# ha_light_swich.net
KiCad netlist of a schematic drawn in Altium Designer
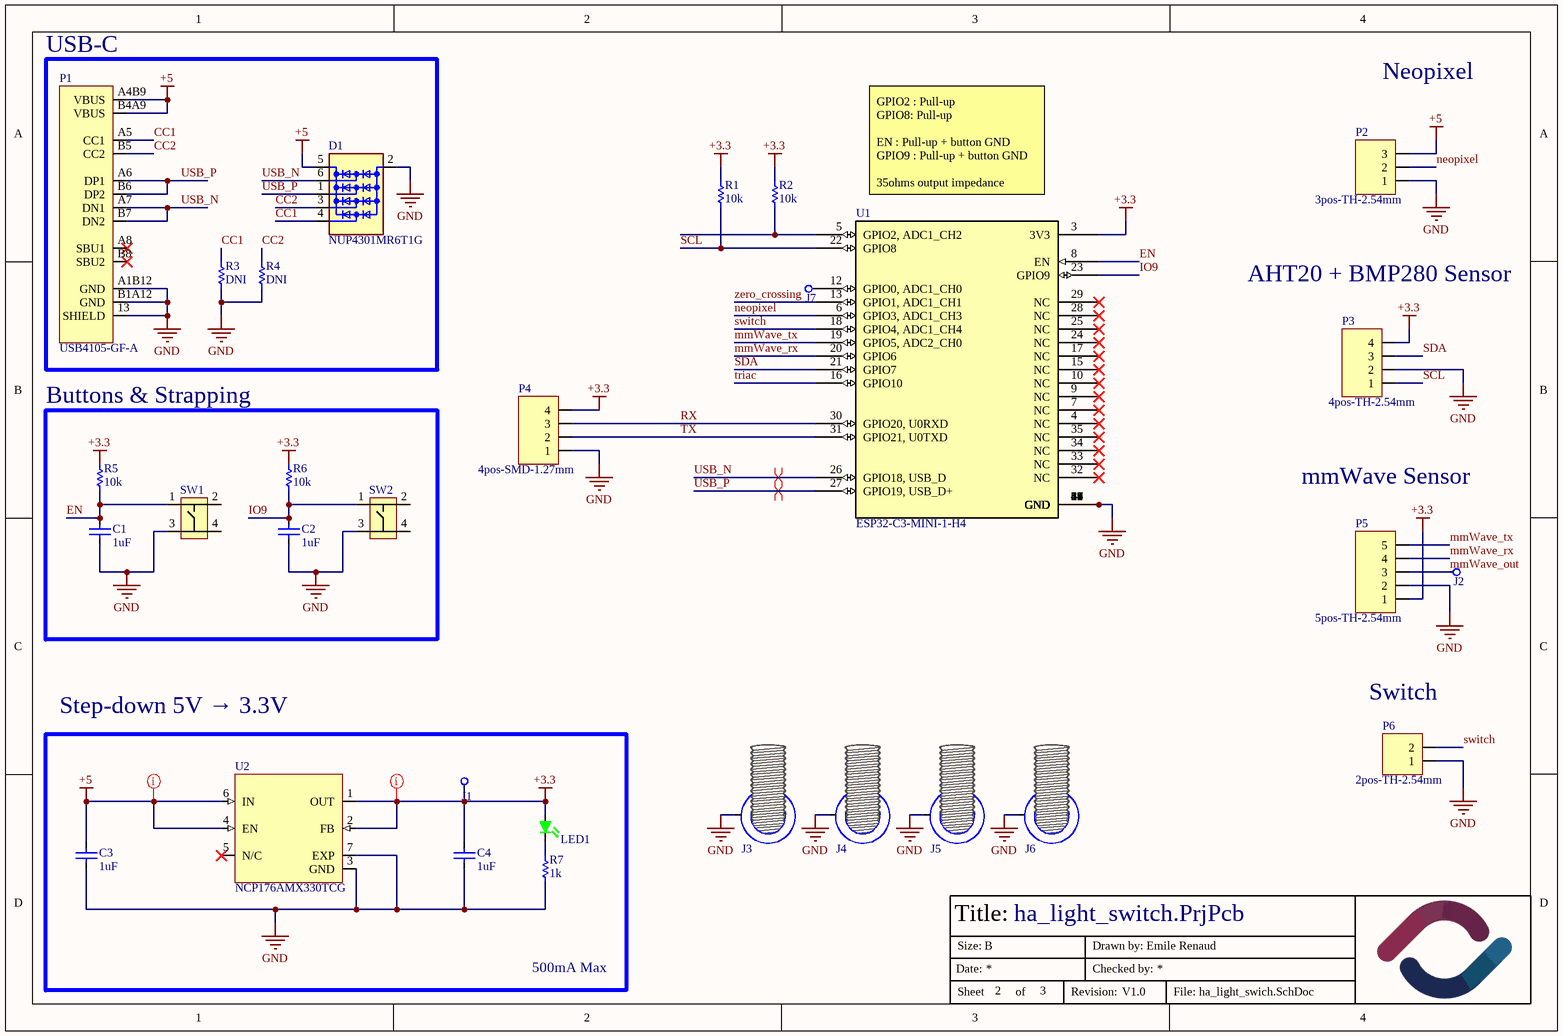
[diagram p0: ha_light_swich.SchDoc]

(export (version "E")
  (design (tool "Eeschema 10.0.6"))
  (components
    (comp (ref "C1")
      (value "1uF")
      (footprint "CAPACITOR-0603")
      (description "Capacitor-0603-1uF-25V-X5R")
      (libsource (lib "Capacitors") (part "Capacitor-0603-1uF-25V-X5R"))
    )
    (comp (ref "C2")
      (value "1uF")
      (footprint "CAPACITOR-0603")
      (description "Capacitor-0603-1uF-25V-X5R")
      (libsource (lib "Capacitors") (part "Capacitor-0603-1uF-25V-X5R"))
    )
    (comp (ref "C3")
      (value "1uF")
      (footprint "CAPACITOR-0603")
      (description "Capacitor-0603-1uF-25V-X5R")
      (libsource (lib "Capacitors") (part "Capacitor-0603-1uF-25V-X5R"))
    )
    (comp (ref "C4")
      (value "1uF")
      (footprint "CAPACITOR-0603")
      (description "Capacitor-0603-1uF-25V-X5R")
      (libsource (lib "Capacitors") (part "Capacitor-0603-1uF-25V-X5R"))
    )
    (comp (ref "D1")
      (value "NUP4301MR6T1G")
      (footprint "SOT-23-6")
      (description "4CH Clamp Ipp Tvs Diode Surface Mount SOT23-6 (SC74)")
      (libsource (lib "diodes") (part "NUP4301MR6T1G"))
    )
    (comp (ref "J1")
      (value "hole")
      (footprint "PAD-1.2MM-silk")
      (libsource (lib "JumpersAndHoles") (part "PAD 1.2mm"))
    )
    (comp (ref "J2")
      (value "hole")
      (footprint "PCB_Footprints:PAD-1.2MM")
      (libsource (lib "JumpersAndHoles") (part "PAD 1.2mm"))
    )
    (comp (ref "J3")
      (value "hole")
      (footprint "HOLE-3.40MM-M3-8MMEYELET")
      (description "Hole for M3 Bolt with 8mm pad")
      (libsource (lib "JumpersAndHoles") (part "Hole 3.40mm M3-Eyelet"))
    )
    (comp (ref "J4")
      (value "hole")
      (footprint "HOLE-3.40MM-M3-8MMEYELET")
      (description "Hole for M3 Bolt with 8mm pad")
      (libsource (lib "JumpersAndHoles") (part "Hole 3.40mm M3-Eyelet"))
    )
    (comp (ref "J5")
      (value "hole")
      (footprint "HOLE-3.40MM-M3-8MMEYELET")
      (description "Hole for M3 Bolt with 8mm pad")
      (libsource (lib "JumpersAndHoles") (part "Hole 3.40mm M3-Eyelet"))
    )
    (comp (ref "J6")
      (value "hole")
      (footprint "HOLE-3.40MM-M3-8MMEYELET")
      (description "Hole for M3 Bolt with 8mm pad")
      (libsource (lib "JumpersAndHoles") (part "Hole 3.40mm M3-Eyelet"))
    )
    (comp (ref "J7")
      (value "hole")
      (footprint "PCB_Footprints:PAD-1.2MM")
      (libsource (lib "JumpersAndHoles") (part "PAD 1.2mm"))
    )
    (comp (ref "LED1")
      (value "3147-B1911NG--20D000214U1930CT-ND")
      (footprint "LED-0603-2PIN-SILKSCREEN")
      (description "LED GREEN DIFFUSED 0603 SMD")
      (libsource (lib "LEDs") (part "LED_GREEN"))
    )
    (comp (ref "P1")
      (value "USB4105-GF-A")
      (footprint "USB-C")
      (description "CONN RCP USB2.0 TYP C 24P SMD RA\r\n5A")
      (libsource (lib "PC-connector") (part "USB4105-GF-A"))
    )
    (comp (ref "P2")
      (value "3pos-TH-2.54mm")
      (footprint "HDR1X3")
      (description "3pos TH 2.54mm Header")
      (libsource (lib "Header") (part "3pos-TH-2.54mm"))
    )
    (comp (ref "P3")
      (value "4pos-TH-2.54mm")
      (footprint "HDR1X4")
      (description "4pos TH 2.54mm Header")
      (libsource (lib "Header") (part "4pos-TH-2.54mm"))
    )
    (comp (ref "P4")
      (value "4pos-SMD-1.27mm")
      (footprint "HDR1X4-SMD-50mils")
      (description "4pos SMD 1.27mm")
      (libsource (lib "Header") (part "4pos-SMD-1.27mm"))
    )
    (comp (ref "P5")
      (value "5pos-TH-2.54mm")
      (footprint "HDR1X5")
      (description "5pos TH 2.54mm Header")
      (libsource (lib "Header") (part "5pos-TH-2.54mm"))
    )
    (comp (ref "P6")
      (value "2pos-TH-2.54mm")
      (footprint "HDR1X2")
      (description "2pos TH 2.54mm Header")
      (libsource (lib "Header") (part "2pos-TH-2.54mm"))
    )
    (comp (ref "R1")
      (value "10k")
      (footprint "Resistor-0603")
      (description "Resistor0603-10k")
      (fields (field (name "Comment") "SMT resistor"))
      (libsource (lib "Resistors") (part "Resistor0603-10k"))
    )
    (comp (ref "R2")
      (value "10k")
      (footprint "Resistor-0603")
      (description "Resistor0603-10k")
      (fields (field (name "Comment") "SMT resistor"))
      (libsource (lib "Resistors") (part "Resistor0603-10k"))
    )
    (comp (ref "R3")
      (value "DNI")
      (footprint "RESISTOR-0603")
      (description "0603 footprint DO NOT INSTALL")
      (fields (field (name "Comment") "Resistor-0603-5.1k"))
      (libsource (lib "Resistors") (part "Resistor-0603-DNI"))
    )
    (comp (ref "R4")
      (value "DNI")
      (footprint "RESISTOR-0603")
      (description "0603 footprint DO NOT INSTALL")
      (fields (field (name "Comment") "Resistor-0603-5.1k"))
      (libsource (lib "Resistors") (part "Resistor-0603-DNI"))
    )
    (comp (ref "R5")
      (value "10k")
      (footprint "Resistor-0603")
      (description "Resistor0603-10k")
      (fields (field (name "Comment") "SMT resistor"))
      (libsource (lib "Resistors") (part "Resistor0603-10k"))
    )
    (comp (ref "R6")
      (value "10k")
      (footprint "Resistor-0603")
      (description "Resistor0603-10k")
      (fields (field (name "Comment") "SMT resistor"))
      (libsource (lib "Resistors") (part "Resistor0603-10k"))
    )
    (comp (ref "R7")
      (value "1k")
      (footprint "Resistor-0603")
      (description "Resistor0603-1k")
      (fields (field (name "Comment") "SMT resistor"))
      (libsource (lib "Resistors") (part "Resistor0603-1k"))
    )
    (comp (ref "SW1")
      (value "PTS815 SJM 250 SMTR LFS")
      (footprint "SW4_PTS815 SJM 250 SMTR LFS_CNK")
      (description "TACT 4.2 X 3.2, 2.5 MM H, 180GF,")
      (libsource (lib "THTPushButtonSwitches") (part "PTS815 SJM 250 SMTR LFS"))
    )
    (comp (ref "SW2")
      (value "PTS815 SJM 250 SMTR LFS")
      (footprint "SW4_PTS815 SJM 250 SMTR LFS_CNK")
      (description "TACT 4.2 X 3.2, 2.5 MM H, 180GF,")
      (libsource (lib "THTPushButtonSwitches") (part "PTS815 SJM 250 SMTR LFS"))
    )
    (comp (ref "U1")
      (value "ESP32-C3-MINI-1-H4")
      (footprint "ESP32-C3-MINI-1_EXP")
      (fields
        (field (name "MANUFACTURER_PART_NUMBER") "ESP32-C3-MINI-1-N4")
        (field (name "COPYRIGHT") "Copyright (C) 2023 Ultra Librarian. All rights reserved.")
      )
      (libsource (lib "Microcontrollers") (part "ESP32-C3-MINI-1-N4"))
    )
    (comp (ref "U2")
      (value "NCP176AMX330TCG")
      (footprint "PCB_Footprints:XFDFN-6 Exposed Pad")
      (description "IC REG LINEAR 3.3V 500mA 6-XDFN")
      (libsource (lib "PMIC-VoltageRegulators-LinearRegulators") (part "NCP176AMX330TCG"))
    )
  )
  (nets
    (net (code "1") (name "+3.3") (class "Default")
      (node (ref "C4") (pin "2") (pinfunction "2_2") (pintype "passive"))
      (node (ref "J1") (pin "1") (pinfunction "1_1") (pintype "passive"))
      (node (ref "LED1") (pin "2") (pinfunction "R_2") (pintype "passive"))
      (node (ref "P3") (pin "4") (pinfunction "4_4") (pintype "passive"))
      (node (ref "P4") (pin "4") (pinfunction "4_4") (pintype "passive"))
      (node (ref "P5") (pin "1") (pinfunction "1_1") (pintype "passive"))
      (node (ref "R1") (pin "2") (pinfunction "2_2") (pintype "passive"))
      (node (ref "R2") (pin "2") (pinfunction "2_2") (pintype "passive"))
      (node (ref "R5") (pin "2") (pinfunction "2_2") (pintype "passive"))
      (node (ref "R6") (pin "2") (pinfunction "2_2") (pintype "passive"))
      (node (ref "U1") (pin "3") (pinfunction "3V3_3") (pintype "power_in"))
      (node (ref "U2") (pin "1") (pinfunction "OUT_1") (pintype "passive"))
      (node (ref "U2") (pin "2") (pinfunction "FB_2") (pintype "input"))
    )
    (net (code "2") (name "+5") (class "Default")
      (node (ref "C3") (pin "2") (pinfunction "2_2") (pintype "passive"))
      (node (ref "D1") (pin "5") (pinfunction "VDD_5") (pintype "passive"))
      (node (ref "P1") (pin "A4B9") (pinfunction "VBUS_A4B9") (pintype "passive"))
      (node (ref "P1") (pin "B4A9") (pinfunction "VBUS_B4A9") (pintype "passive"))
      (node (ref "P2") (pin "3") (pinfunction "3_3") (pintype "passive"))
      (node (ref "U2") (pin "4") (pinfunction "EN_4") (pintype "input"))
      (node (ref "U2") (pin "6") (pinfunction "IN_6") (pintype "input"))
    )
    (net (code "3") (name "/CC1") (class "Default")
      (node (ref "D1") (pin "4") (pinfunction "L4_4") (pintype "passive"))
      (node (ref "P1") (pin "A5") (pinfunction "CC1_A5") (pintype "passive"))
      (node (ref "R3") (pin "2") (pinfunction "2_2") (pintype "passive"))
    )
    (net (code "4") (name "/CC2") (class "Default")
      (node (ref "D1") (pin "3") (pinfunction "L3_3") (pintype "passive"))
      (node (ref "P1") (pin "B5") (pinfunction "CC2_B5") (pintype "passive"))
      (node (ref "R4") (pin "2") (pinfunction "2_2") (pintype "passive"))
    )
    (net (code "5") (name "/EN") (class "Default")
      (node (ref "C1") (pin "2") (pinfunction "2_2") (pintype "passive"))
      (node (ref "R5") (pin "1") (pinfunction "1_1") (pintype "passive"))
      (node (ref "SW1") (pin "1") (pinfunction "1_1") (pintype "passive"))
      (node (ref "U1") (pin "8") (pinfunction "EN_8") (pintype "input"))
    )
    (net (code "6") (name "/IO9") (class "Default")
      (node (ref "C2") (pin "2") (pinfunction "2_2") (pintype "passive"))
      (node (ref "R6") (pin "1") (pinfunction "1_1") (pintype "passive"))
      (node (ref "SW2") (pin "1") (pinfunction "1_1") (pintype "passive"))
      (node (ref "U1") (pin "23") (pinfunction "GPIO9_23") (pintype "bidirectional"))
    )
    (net (code "7") (name "/RX") (class "Default")
      (node (ref "P4") (pin "3") (pinfunction "3_3") (pintype "passive"))
      (node (ref "U1") (pin "30") (pinfunction "GPIO20,_U0RXD_30") (pintype "bidirectional"))
    )
    (net (code "8") (name "/SCL") (class "Default")
      (node (ref "P3") (pin "1") (pinfunction "1_1") (pintype "passive"))
      (node (ref "R1") (pin "1") (pinfunction "1_1") (pintype "passive"))
      (node (ref "U1") (pin "22") (pinfunction "GPIO8_22") (pintype "bidirectional"))
    )
    (net (code "9") (name "/SDA") (class "Default")
      (node (ref "P3") (pin "3") (pinfunction "3_3") (pintype "passive"))
      (node (ref "U1") (pin "21") (pinfunction "GPIO7_21") (pintype "bidirectional"))
    )
    (net (code "10") (name "/TX") (class "Default")
      (node (ref "P4") (pin "2") (pinfunction "2_2") (pintype "passive"))
      (node (ref "U1") (pin "31") (pinfunction "GPIO21,_U0TXD_31") (pintype "bidirectional"))
    )
    (net (code "11") (name "/USB_N") (class "Default")
      (node (ref "D1") (pin "6") (pinfunction "L1_6") (pintype "passive"))
      (node (ref "P1") (pin "A7") (pinfunction "DN1_A7") (pintype "passive"))
      (node (ref "P1") (pin "B7") (pinfunction "DN2_B7") (pintype "passive"))
      (node (ref "U1") (pin "26") (pinfunction "GPIO18,_USB_D_26") (pintype "bidirectional"))
    )
    (net (code "12") (name "/USB_P") (class "Default")
      (node (ref "D1") (pin "1") (pinfunction "L2_1") (pintype "passive"))
      (node (ref "P1") (pin "A6") (pinfunction "DP1_A6") (pintype "passive"))
      (node (ref "P1") (pin "B6") (pinfunction "DP2_B6") (pintype "passive"))
      (node (ref "U1") (pin "27") (pinfunction "GPIO19,_USB_D+_27") (pintype "bidirectional"))
    )
    (net (code "13") (name "/mmWave_out") (class "Default")
      (node (ref "J2") (pin "1") (pinfunction "1_1") (pintype "passive"))
      (node (ref "P5") (pin "3") (pinfunction "3_3") (pintype "passive"))
    )
    (net (code "14") (name "/mmWave_rx") (class "Default")
      (node (ref "P5") (pin "4") (pinfunction "4_4") (pintype "passive"))
      (node (ref "U1") (pin "20") (pinfunction "GPIO6_20") (pintype "bidirectional"))
    )
    (net (code "15") (name "/mmWave_tx") (class "Default")
      (node (ref "P5") (pin "5") (pinfunction "5_5") (pintype "passive"))
      (node (ref "U1") (pin "19") (pinfunction "GPIO5,_ADC2_CH0_19") (pintype "bidirectional"))
    )
    (net (code "16") (name "/neopixel") (class "Default")
      (node (ref "P2") (pin "2") (pinfunction "2_2") (pintype "passive"))
      (node (ref "U1") (pin "6") (pinfunction "GPIO3,_ADC1_CH3_6") (pintype "bidirectional"))
    )
    (net (code "17") (name "/switch") (class "Default")
      (node (ref "P6") (pin "2") (pinfunction "2_2") (pintype "passive"))
      (node (ref "U1") (pin "18") (pinfunction "GPIO4,_ADC1_CH4_18") (pintype "bidirectional"))
    )
    (net (code "18") (name "/triac") (class "Default")
      (node (ref "U1") (pin "16") (pinfunction "GPIO10_16") (pintype "bidirectional"))
    )
    (net (code "19") (name "/zero_crossing") (class "Default")
      (node (ref "U1") (pin "13") (pinfunction "GPIO1,_ADC1_CH1_13") (pintype "bidirectional"))
    )
    (net (code "20") (name "GND") (class "Default")
      (node (ref "C1") (pin "1") (pinfunction "1_1") (pintype "passive"))
      (node (ref "C2") (pin "1") (pinfunction "1_1") (pintype "passive"))
      (node (ref "C3") (pin "1") (pinfunction "1_1") (pintype "passive"))
      (node (ref "C4") (pin "1") (pinfunction "1_1") (pintype "passive"))
      (node (ref "D1") (pin "2") (pinfunction "GND_2") (pintype "passive"))
      (node (ref "J3") (pin "1") (pinfunction "1_1") (pintype "passive"))
      (node (ref "J4") (pin "1") (pinfunction "1_1") (pintype "passive"))
      (node (ref "J5") (pin "1") (pinfunction "1_1") (pintype "passive"))
      (node (ref "J6") (pin "1") (pinfunction "1_1") (pintype "passive"))
      (node (ref "P1") (pin "13") (pinfunction "SHIELD_13") (pintype "passive"))
      (node (ref "P1") (pin "A1B12") (pinfunction "GND_A1B12") (pintype "passive"))
      (node (ref "P1") (pin "B1A12") (pinfunction "GND_B1A12") (pintype "passive"))
      (node (ref "P2") (pin "1") (pinfunction "1_1") (pintype "passive"))
      (node (ref "P3") (pin "2") (pinfunction "2_2") (pintype "passive"))
      (node (ref "P4") (pin "1") (pinfunction "1_1") (pintype "passive"))
      (node (ref "P5") (pin "2") (pinfunction "2_2") (pintype "passive"))
      (node (ref "P6") (pin "1") (pinfunction "1_1") (pintype "passive"))
      (node (ref "R3") (pin "1") (pinfunction "1_1") (pintype "passive"))
      (node (ref "R4") (pin "1") (pinfunction "1_1") (pintype "passive"))
      (node (ref "R7") (pin "1") (pinfunction "1_1") (pintype "passive"))
      (node (ref "SW1") (pin "3") (pinfunction "3_3") (pintype "passive"))
      (node (ref "SW2") (pin "3") (pinfunction "3_3") (pintype "passive"))
      (node (ref "U1") (pin "1") (pinfunction "GND_1") (pintype "passive"))
      (node (ref "U1") (pin "11") (pinfunction "GND_11") (pintype "passive"))
      (node (ref "U1") (pin "14") (pinfunction "GND_14") (pintype "passive"))
      (node (ref "U1") (pin "2") (pinfunction "GND_2") (pintype "passive"))
      (node (ref "U1") (pin "36") (pinfunction "GND_36") (pintype "passive"))
      (node (ref "U1") (pin "37") (pinfunction "GND_37") (pintype "passive"))
      (node (ref "U1") (pin "38") (pinfunction "GND_38") (pintype "passive"))
      (node (ref "U1") (pin "39") (pinfunction "GND_39") (pintype "passive"))
      (node (ref "U1") (pin "40") (pinfunction "GND_40") (pintype "passive"))
      (node (ref "U1") (pin "41") (pinfunction "GND_41") (pintype "passive"))
      (node (ref "U1") (pin "42") (pinfunction "GND_42") (pintype "passive"))
      (node (ref "U1") (pin "43") (pinfunction "GND_43") (pintype "passive"))
      (node (ref "U1") (pin "44") (pinfunction "GND_44") (pintype "passive"))
      (node (ref "U1") (pin "45") (pinfunction "GND_45") (pintype "passive"))
      (node (ref "U1") (pin "46") (pinfunction "GND_46") (pintype "passive"))
      (node (ref "U1") (pin "47") (pinfunction "GND_47") (pintype "passive"))
      (node (ref "U1") (pin "48") (pinfunction "GND_48") (pintype "passive"))
      (node (ref "U1") (pin "49") (pinfunction "GND_49") (pintype "passive"))
      (node (ref "U1") (pin "50") (pinfunction "GND_50") (pintype "passive"))
      (node (ref "U1") (pin "51") (pinfunction "GND_51") (pintype "passive"))
      (node (ref "U1") (pin "52") (pinfunction "GND_52") (pintype "passive"))
      (node (ref "U1") (pin "53") (pinfunction "GND_53") (pintype "passive"))
      (node (ref "U1") (pin "54") (pinfunction "GND_54") (pintype "passive"))
      (node (ref "U1") (pin "55") (pinfunction "GND_55") (pintype "passive"))
      (node (ref "U1") (pin "56") (pinfunction "GND_56") (pintype "passive"))
      (node (ref "U1") (pin "57") (pinfunction "GND_57") (pintype "passive"))
      (node (ref "U1") (pin "58") (pinfunction "GND_58") (pintype "passive"))
      (node (ref "U1") (pin "59") (pinfunction "GND_59") (pintype "passive"))
      (node (ref "U1") (pin "60") (pinfunction "GND_60") (pintype "passive"))
      (node (ref "U1") (pin "61") (pinfunction "GND_61") (pintype "passive"))
      (node (ref "U2") (pin "3") (pinfunction "GND_3") (pintype "power_in"))
      (node (ref "U2") (pin "7") (pinfunction "EXP_7") (pintype "power_in"))
    )
    (net (code "21") (name "Net-(LED1-K)") (class "Default")
      (node (ref "LED1") (pin "1") (pinfunction "K_1") (pintype "passive"))
      (node (ref "R7") (pin "2") (pinfunction "2_2") (pintype "passive"))
    )
    (net (code "22") (name "Net-(U1-GPIO0,_ADC1_CH0)") (class "Default")
      (node (ref "J7") (pin "1") (pinfunction "1_1") (pintype "passive"))
      (node (ref "U1") (pin "12") (pinfunction "GPIO0,_ADC1_CH0_12") (pintype "bidirectional"))
    )
    (net (code "23") (name "Net-(U1-GPIO2,_ADC1_CH2)") (class "Default")
      (node (ref "R2") (pin "1") (pinfunction "1_1") (pintype "passive"))
      (node (ref "U1") (pin "5") (pinfunction "GPIO2,_ADC1_CH2_5") (pintype "bidirectional"))
    )
    (net (code "24") (name "unconnected-(P1-SBU1-PadA8)") (class "Default")
      (node (ref "P1") (pin "A8") (pinfunction "SBU1_A8") (pintype "passive+no_connect"))
    )
    (net (code "25") (name "unconnected-(P1-SBU2-PadB8)") (class "Default")
      (node (ref "P1") (pin "B8") (pinfunction "SBU2_B8") (pintype "passive+no_connect"))
    )
    (net (code "26") (name "unconnected-(SW1-Pad2)") (class "Default")
      (node (ref "SW1") (pin "2") (pinfunction "2_2") (pintype "passive"))
    )
    (net (code "27") (name "unconnected-(SW1-Pad4)") (class "Default")
      (node (ref "SW1") (pin "4") (pinfunction "4_4") (pintype "passive"))
    )
    (net (code "28") (name "unconnected-(SW2-Pad2)") (class "Default")
      (node (ref "SW2") (pin "2") (pinfunction "2_2") (pintype "passive"))
    )
    (net (code "29") (name "unconnected-(SW2-Pad4)") (class "Default")
      (node (ref "SW2") (pin "4") (pinfunction "4_4") (pintype "passive"))
    )
    (net (code "30") (name "unconnected-(U1-NC-Pad4)") (class "Default")
      (node (ref "U1") (pin "4") (pinfunction "NC_4") (pintype "passive+no_connect"))
    )
    (net (code "31") (name "unconnected-(U1-NC-Pad7)") (class "Default")
      (node (ref "U1") (pin "7") (pinfunction "NC_7") (pintype "passive+no_connect"))
    )
    (net (code "32") (name "unconnected-(U1-NC-Pad9)") (class "Default")
      (node (ref "U1") (pin "9") (pinfunction "NC_9") (pintype "passive+no_connect"))
    )
    (net (code "33") (name "unconnected-(U1-NC-Pad10)") (class "Default")
      (node (ref "U1") (pin "10") (pinfunction "NC_10") (pintype "passive+no_connect"))
    )
    (net (code "34") (name "unconnected-(U1-NC-Pad15)") (class "Default")
      (node (ref "U1") (pin "15") (pinfunction "NC_15") (pintype "passive+no_connect"))
    )
    (net (code "35") (name "unconnected-(U1-NC-Pad17)") (class "Default")
      (node (ref "U1") (pin "17") (pinfunction "NC_17") (pintype "passive+no_connect"))
    )
    (net (code "36") (name "unconnected-(U1-NC-Pad24)") (class "Default")
      (node (ref "U1") (pin "24") (pinfunction "NC_24") (pintype "passive+no_connect"))
    )
    (net (code "37") (name "unconnected-(U1-NC-Pad25)") (class "Default")
      (node (ref "U1") (pin "25") (pinfunction "NC_25") (pintype "passive+no_connect"))
    )
    (net (code "38") (name "unconnected-(U1-NC-Pad28)") (class "Default")
      (node (ref "U1") (pin "28") (pinfunction "NC_28") (pintype "passive+no_connect"))
    )
    (net (code "39") (name "unconnected-(U1-NC-Pad29)") (class "Default")
      (node (ref "U1") (pin "29") (pinfunction "NC_29") (pintype "passive+no_connect"))
    )
    (net (code "40") (name "unconnected-(U1-NC-Pad32)") (class "Default")
      (node (ref "U1") (pin "32") (pinfunction "NC_32") (pintype "passive+no_connect"))
    )
    (net (code "41") (name "unconnected-(U1-NC-Pad33)") (class "Default")
      (node (ref "U1") (pin "33") (pinfunction "NC_33") (pintype "passive+no_connect"))
    )
    (net (code "42") (name "unconnected-(U1-NC-Pad34)") (class "Default")
      (node (ref "U1") (pin "34") (pinfunction "NC_34") (pintype "passive+no_connect"))
    )
    (net (code "43") (name "unconnected-(U1-NC-Pad35)") (class "Default")
      (node (ref "U1") (pin "35") (pinfunction "NC_35") (pintype "passive+no_connect"))
    )
    (net (code "44") (name "unconnected-(U2-N{slash}C-Pad5)") (class "Default")
      (node (ref "U2") (pin "5") (pinfunction "N/C_5") (pintype "passive+no_connect"))
    )
  )
)
